# FMC_HPC_TO_LPC_BREAKOUT_REVA.net
KiCad netlist of a schematic drawn in Altium Designer
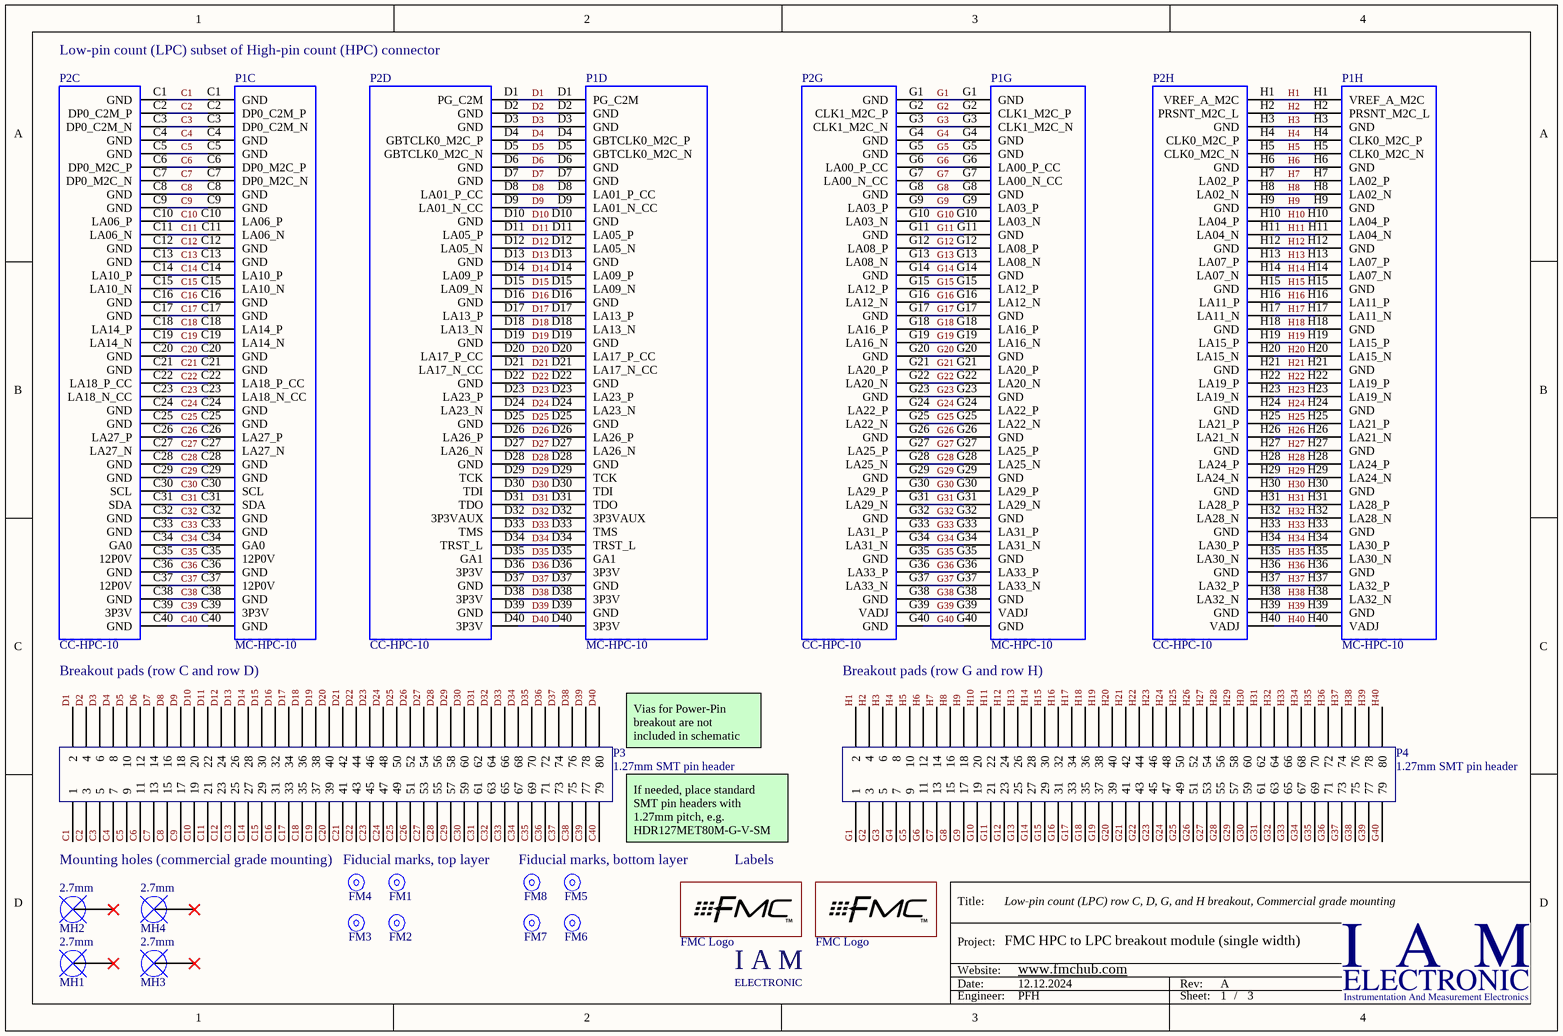
[diagram p0: FMC_HPC_TO_LPC_BREAKOUT_REVA.SchDoc]

(export (version "E")
  (design (tool "Eeschema 10.0.6"))
  (components
    (comp (ref "FM1")
      (value "1mm")
      (footprint "FIDUCIAL_MARK_ROUND_RING")
      (description "Fiducial mark, width 1mm, clearance 3mm")
      (libsource (lib "VITA_57_FMC") (part "Fiducial_Mark"))
    )
    (comp (ref "FM2")
      (value "1mm")
      (footprint "FIDUCIAL_MARK_ROUND_RING")
      (description "Fiducial mark, width 1mm, clearance 3mm")
      (libsource (lib "VITA_57_FMC") (part "Fiducial_Mark"))
    )
    (comp (ref "FM3")
      (value "1mm")
      (footprint "FIDUCIAL_MARK_ROUND_RING")
      (description "Fiducial mark, width 1mm, clearance 3mm")
      (libsource (lib "VITA_57_FMC") (part "Fiducial_Mark"))
    )
    (comp (ref "FM4")
      (value "1mm")
      (footprint "FIDUCIAL_MARK_ROUND_RING")
      (description "Fiducial mark, width 1mm, clearance 3mm")
      (libsource (lib "VITA_57_FMC") (part "Fiducial_Mark"))
    )
    (comp (ref "FM5")
      (value "1mm")
      (footprint "FIDUCIAL_MARK_ROUND_RING")
      (description "Fiducial mark, width 1mm, clearance 3mm")
      (libsource (lib "VITA_57_FMC") (part "Fiducial_Mark"))
    )
    (comp (ref "FM6")
      (value "1mm")
      (footprint "FIDUCIAL_MARK_ROUND_RING")
      (description "Fiducial mark, width 1mm, clearance 3mm")
      (libsource (lib "VITA_57_FMC") (part "Fiducial_Mark"))
    )
    (comp (ref "FM7")
      (value "1mm")
      (footprint "FIDUCIAL_MARK_ROUND_RING")
      (description "Fiducial mark, width 1mm, clearance 3mm")
      (libsource (lib "VITA_57_FMC") (part "Fiducial_Mark"))
    )
    (comp (ref "FM8")
      (value "1mm")
      (footprint "FIDUCIAL_MARK_ROUND_RING")
      (description "Fiducial mark, width 1mm, clearance 3mm")
      (libsource (lib "VITA_57_FMC") (part "Fiducial_Mark"))
    )
    (comp (ref "MH1")
      (value "2.7mm")
      (footprint "Mounting_Hole_Plated_2.7mm - d3.1mm")
      (description "Mounting hole, hole size 2.7mm")
      (libsource (lib "VITA_57_FMC") (part "Mounting_Hole_2.7mm"))
    )
    (comp (ref "MH2")
      (value "2.7mm")
      (footprint "Mounting_Hole_Plated_2.7mm - d3.1mm")
      (description "Mounting hole, hole size 2.7mm")
      (libsource (lib "VITA_57_FMC") (part "Mounting_Hole_2.7mm"))
    )
    (comp (ref "MH3")
      (value "2.7mm")
      (footprint "Mounting_Hole_Plated_2.7mm-COVERED")
      (description "Mounting hole, hole size 2.7mm")
      (libsource (lib "VITA_57_FMC") (part "Mounting_Hole_2.7mm"))
    )
    (comp (ref "MH4")
      (value "2.7mm")
      (footprint "Mounting_Hole_Plated_2.7mm-COVERED")
      (description "Mounting hole, hole size 2.7mm")
      (libsource (lib "VITA_57_FMC") (part "Mounting_Hole_2.7mm"))
    )
    (comp (ref "P1")
      (value "MC-HPC-10")
      (footprint "ASP-134488-01")
      (description "MC-HPC-10, FMC High-pin count connector, lead free, 400 I/Os, male, 10 mm mated stack height")
      (fields (field (name "MANUFACTURER") "Samtec") (field (name "PART") "ASP-134488-01"))
      (libsource (lib "VITA_57_FMC") (part "MC-HPC-10"))
    )
    (comp (ref "P2")
      (value "CC-HPC-10")
      (footprint "ASP-134486-01")
      (description "CC-HPC-10, FMC High-pin count connector, lead free, 400 I/Os, female, 10 mm mated stack height")
      (fields (field (name "MANUFACTURER") "Samtec") (field (name "PART") "ASP-134486-01"))
      (libsource (lib "VITA_57_FMC") (part "CC-HPC-10"))
    )
    (comp (ref "P3")
      (value "1.27mm SMT pin header")
      (footprint "FTS-140-01-L-DV-A_NO_PASTE")
      (description "1.27 MM 80 PIN VERTICAL MALE HEADER")
      (fields (field (name "PART") "FTS-140-01-L-DV-A") (field (name "MANUFACTURER") "Samtec"))
      (libsource (lib "FTS-140") (part "FTS-140-X-DV"))
    )
    (comp (ref "P4")
      (value "1.27mm SMT pin header")
      (footprint "FTS-140-01-L-DV-A_NO_PASTE")
      (description "1.27 MM 80 PIN VERTICAL MALE HEADER")
      (fields (field (name "PART") "FTS-140-01-L-DV-A") (field (name "MANUFACTURER") "Samtec"))
      (libsource (lib "FTS-140") (part "FTS-140-X-DV"))
    )
    (comp (ref "STR1")
      (value "IAM LOGO")
      (footprint "IAM LOGO - MEDIUM")
      (description "I A M E L E C T R O N I C - Logo")
      (fields (field (name "MANUFACTURER") "IAM ELECTRONIC") (field (name "PART") "Logo"))
      (libsource (lib "IAM_LOGOS") (part "IAM_LOGO"))
    )
    (comp (ref "STR2")
      (value "FMC Logo")
      (footprint "FMC_TM_LOGO_SMALL")
      (description "VITA FMC Logo")
      (libsource (lib "VITA_57_FMC") (part "FMC_Logo"))
    )
    (comp (ref "STR3")
      (value "FMC Logo")
      (footprint "FMC_TM_LOGO_SMALL")
      (description "VITA FMC Logo")
      (libsource (lib "VITA_57_FMC") (part "FMC_Logo"))
    )
  )
  (nets
    (net (code "1") (name "/C1") (class "Default")
      (node (ref "P1") (pin "C1") (pinfunction "GND_C1") (pintype "passive"))
      (node (ref "P2") (pin "C1") (pinfunction "GND_C1") (pintype "passive"))
      (node (ref "P3") (pin "1") (pinfunction "1_1") (pintype "passive"))
    )
    (net (code "2") (name "/C2") (class "Default")
      (node (ref "P1") (pin "C2") (pinfunction "DP0_C2M_P_C2") (pintype "passive"))
      (node (ref "P2") (pin "C2") (pinfunction "DP0_C2M_P_C2") (pintype "passive"))
      (node (ref "P3") (pin "3") (pinfunction "3_3") (pintype "passive"))
    )
    (net (code "3") (name "/C3") (class "Default")
      (node (ref "P1") (pin "C3") (pinfunction "DP0_C2M_N_C3") (pintype "passive"))
      (node (ref "P2") (pin "C3") (pinfunction "DP0_C2M_N_C3") (pintype "passive"))
      (node (ref "P3") (pin "5") (pinfunction "5_5") (pintype "passive"))
    )
    (net (code "4") (name "/C4") (class "Default")
      (node (ref "P1") (pin "C4") (pinfunction "GND_C4") (pintype "passive"))
      (node (ref "P2") (pin "C4") (pinfunction "GND_C4") (pintype "passive"))
      (node (ref "P3") (pin "7") (pinfunction "7_7") (pintype "passive"))
    )
    (net (code "5") (name "/C5") (class "Default")
      (node (ref "P1") (pin "C5") (pinfunction "GND_C5") (pintype "passive"))
      (node (ref "P2") (pin "C5") (pinfunction "GND_C5") (pintype "passive"))
      (node (ref "P3") (pin "9") (pinfunction "9_9") (pintype "passive"))
    )
    (net (code "6") (name "/C6") (class "Default")
      (node (ref "P1") (pin "C6") (pinfunction "DP0_M2C_P_C6") (pintype "passive"))
      (node (ref "P2") (pin "C6") (pinfunction "DP0_M2C_P_C6") (pintype "passive"))
      (node (ref "P3") (pin "11") (pinfunction "11_11") (pintype "passive"))
    )
    (net (code "7") (name "/C7") (class "Default")
      (node (ref "P1") (pin "C7") (pinfunction "DP0_M2C_N_C7") (pintype "passive"))
      (node (ref "P2") (pin "C7") (pinfunction "DP0_M2C_N_C7") (pintype "passive"))
      (node (ref "P3") (pin "13") (pinfunction "13_13") (pintype "passive"))
    )
    (net (code "8") (name "/C8") (class "Default")
      (node (ref "P1") (pin "C8") (pinfunction "GND_C8") (pintype "passive"))
      (node (ref "P2") (pin "C8") (pinfunction "GND_C8") (pintype "passive"))
      (node (ref "P3") (pin "15") (pinfunction "15_15") (pintype "passive"))
    )
    (net (code "9") (name "/C9") (class "Default")
      (node (ref "P1") (pin "C9") (pinfunction "GND_C9") (pintype "passive"))
      (node (ref "P2") (pin "C9") (pinfunction "GND_C9") (pintype "passive"))
      (node (ref "P3") (pin "17") (pinfunction "17_17") (pintype "passive"))
    )
    (net (code "10") (name "/C10") (class "Default")
      (node (ref "P1") (pin "C10") (pinfunction "LA06_P_C10") (pintype "passive"))
      (node (ref "P2") (pin "C10") (pinfunction "LA06_P_C10") (pintype "passive"))
      (node (ref "P3") (pin "19") (pinfunction "19_19") (pintype "passive"))
    )
    (net (code "11") (name "/C11") (class "Default")
      (node (ref "P1") (pin "C11") (pinfunction "LA06_N_C11") (pintype "passive"))
      (node (ref "P2") (pin "C11") (pinfunction "LA06_N_C11") (pintype "passive"))
      (node (ref "P3") (pin "21") (pinfunction "21_21") (pintype "passive"))
    )
    (net (code "12") (name "/C12") (class "Default")
      (node (ref "P1") (pin "C12") (pinfunction "GND_C12") (pintype "passive"))
      (node (ref "P2") (pin "C12") (pinfunction "GND_C12") (pintype "passive"))
      (node (ref "P3") (pin "23") (pinfunction "23_23") (pintype "passive"))
    )
    (net (code "13") (name "/C13") (class "Default")
      (node (ref "P1") (pin "C13") (pinfunction "GND_C13") (pintype "passive"))
      (node (ref "P2") (pin "C13") (pinfunction "GND_C13") (pintype "passive"))
      (node (ref "P3") (pin "25") (pinfunction "25_25") (pintype "passive"))
    )
    (net (code "14") (name "/C14") (class "Default")
      (node (ref "P1") (pin "C14") (pinfunction "LA10_P_C14") (pintype "passive"))
      (node (ref "P2") (pin "C14") (pinfunction "LA10_P_C14") (pintype "passive"))
      (node (ref "P3") (pin "27") (pinfunction "27_27") (pintype "passive"))
    )
    (net (code "15") (name "/C15") (class "Default")
      (node (ref "P1") (pin "C15") (pinfunction "LA10_N_C15") (pintype "passive"))
      (node (ref "P2") (pin "C15") (pinfunction "LA10_N_C15") (pintype "passive"))
      (node (ref "P3") (pin "29") (pinfunction "29_29") (pintype "passive"))
    )
    (net (code "16") (name "/C16") (class "Default")
      (node (ref "P1") (pin "C16") (pinfunction "GND_C16") (pintype "passive"))
      (node (ref "P2") (pin "C16") (pinfunction "GND_C16") (pintype "passive"))
      (node (ref "P3") (pin "31") (pinfunction "31_31") (pintype "passive"))
    )
    (net (code "17") (name "/C17") (class "Default")
      (node (ref "P1") (pin "C17") (pinfunction "GND_C17") (pintype "passive"))
      (node (ref "P2") (pin "C17") (pinfunction "GND_C17") (pintype "passive"))
      (node (ref "P3") (pin "33") (pinfunction "33_33") (pintype "passive"))
    )
    (net (code "18") (name "/C18") (class "Default")
      (node (ref "P1") (pin "C18") (pinfunction "LA14_P_C18") (pintype "passive"))
      (node (ref "P2") (pin "C18") (pinfunction "LA14_P_C18") (pintype "passive"))
      (node (ref "P3") (pin "35") (pinfunction "35_35") (pintype "passive"))
    )
    (net (code "19") (name "/C19") (class "Default")
      (node (ref "P1") (pin "C19") (pinfunction "LA14_N_C19") (pintype "passive"))
      (node (ref "P2") (pin "C19") (pinfunction "LA14_N_C19") (pintype "passive"))
      (node (ref "P3") (pin "37") (pinfunction "37_37") (pintype "passive"))
    )
    (net (code "20") (name "/C20") (class "Default")
      (node (ref "P1") (pin "C20") (pinfunction "GND_C20") (pintype "passive"))
      (node (ref "P2") (pin "C20") (pinfunction "GND_C20") (pintype "passive"))
      (node (ref "P3") (pin "39") (pinfunction "39_39") (pintype "passive"))
    )
    (net (code "21") (name "/C21") (class "Default")
      (node (ref "P1") (pin "C21") (pinfunction "GND_C21") (pintype "passive"))
      (node (ref "P2") (pin "C21") (pinfunction "GND_C21") (pintype "passive"))
      (node (ref "P3") (pin "41") (pinfunction "41_41") (pintype "passive"))
    )
    (net (code "22") (name "/C22") (class "Default")
      (node (ref "P1") (pin "C22") (pinfunction "LA18_P_CC_C22") (pintype "passive"))
      (node (ref "P2") (pin "C22") (pinfunction "LA18_P_CC_C22") (pintype "passive"))
      (node (ref "P3") (pin "43") (pinfunction "43_43") (pintype "passive"))
    )
    (net (code "23") (name "/C23") (class "Default")
      (node (ref "P1") (pin "C23") (pinfunction "LA18_N_CC_C23") (pintype "passive"))
      (node (ref "P2") (pin "C23") (pinfunction "LA18_N_CC_C23") (pintype "passive"))
      (node (ref "P3") (pin "45") (pinfunction "45_45") (pintype "passive"))
    )
    (net (code "24") (name "/C24") (class "Default")
      (node (ref "P1") (pin "C24") (pinfunction "GND_C24") (pintype "passive"))
      (node (ref "P2") (pin "C24") (pinfunction "GND_C24") (pintype "passive"))
      (node (ref "P3") (pin "47") (pinfunction "47_47") (pintype "passive"))
    )
    (net (code "25") (name "/C25") (class "Default")
      (node (ref "P1") (pin "C25") (pinfunction "GND_C25") (pintype "passive"))
      (node (ref "P2") (pin "C25") (pinfunction "GND_C25") (pintype "passive"))
      (node (ref "P3") (pin "49") (pinfunction "49_49") (pintype "passive"))
    )
    (net (code "26") (name "/C26") (class "Default")
      (node (ref "P1") (pin "C26") (pinfunction "LA27_P_C26") (pintype "passive"))
      (node (ref "P2") (pin "C26") (pinfunction "LA27_P_C26") (pintype "passive"))
      (node (ref "P3") (pin "51") (pinfunction "51_51") (pintype "passive"))
    )
    (net (code "27") (name "/C27") (class "Default")
      (node (ref "P1") (pin "C27") (pinfunction "LA27_N_C27") (pintype "passive"))
      (node (ref "P2") (pin "C27") (pinfunction "LA27_N_C27") (pintype "passive"))
      (node (ref "P3") (pin "53") (pinfunction "53_53") (pintype "passive"))
    )
    (net (code "28") (name "/C28") (class "Default")
      (node (ref "P1") (pin "C28") (pinfunction "GND_C28") (pintype "passive"))
      (node (ref "P2") (pin "C28") (pinfunction "GND_C28") (pintype "passive"))
      (node (ref "P3") (pin "55") (pinfunction "55_55") (pintype "passive"))
    )
    (net (code "29") (name "/C29") (class "Default")
      (node (ref "P1") (pin "C29") (pinfunction "GND_C29") (pintype "passive"))
      (node (ref "P2") (pin "C29") (pinfunction "GND_C29") (pintype "passive"))
      (node (ref "P3") (pin "57") (pinfunction "57_57") (pintype "passive"))
    )
    (net (code "30") (name "/C30") (class "Default")
      (node (ref "P1") (pin "C30") (pinfunction "SCL_C30") (pintype "passive"))
      (node (ref "P2") (pin "C30") (pinfunction "SCL_C30") (pintype "passive"))
      (node (ref "P3") (pin "59") (pinfunction "59_59") (pintype "passive"))
    )
    (net (code "31") (name "/C31") (class "Default")
      (node (ref "P1") (pin "C31") (pinfunction "SDA_C31") (pintype "passive"))
      (node (ref "P2") (pin "C31") (pinfunction "SDA_C31") (pintype "passive"))
      (node (ref "P3") (pin "61") (pinfunction "61_61") (pintype "passive"))
    )
    (net (code "32") (name "/C32") (class "Default")
      (node (ref "P1") (pin "C32") (pinfunction "GND_C32") (pintype "passive"))
      (node (ref "P2") (pin "C32") (pinfunction "GND_C32") (pintype "passive"))
      (node (ref "P3") (pin "63") (pinfunction "63_63") (pintype "passive"))
    )
    (net (code "33") (name "/C33") (class "Default")
      (node (ref "P1") (pin "C33") (pinfunction "GND_C33") (pintype "passive"))
      (node (ref "P2") (pin "C33") (pinfunction "GND_C33") (pintype "passive"))
      (node (ref "P3") (pin "65") (pinfunction "65_65") (pintype "passive"))
    )
    (net (code "34") (name "/C34") (class "Default")
      (node (ref "P1") (pin "C34") (pinfunction "GA0_C34") (pintype "passive"))
      (node (ref "P2") (pin "C34") (pinfunction "GA0_C34") (pintype "passive"))
      (node (ref "P3") (pin "67") (pinfunction "67_67") (pintype "passive"))
    )
    (net (code "35") (name "/C35") (class "Default")
      (node (ref "P1") (pin "C35") (pinfunction "12P0V_C35") (pintype "passive"))
      (node (ref "P2") (pin "C35") (pinfunction "12P0V_C35") (pintype "passive"))
      (node (ref "P3") (pin "69") (pinfunction "69_69") (pintype "passive"))
    )
    (net (code "36") (name "/C36") (class "Default")
      (node (ref "P1") (pin "C36") (pinfunction "GND_C36") (pintype "passive"))
      (node (ref "P2") (pin "C36") (pinfunction "GND_C36") (pintype "passive"))
      (node (ref "P3") (pin "71") (pinfunction "71_71") (pintype "passive"))
    )
    (net (code "37") (name "/C37") (class "Default")
      (node (ref "P1") (pin "C37") (pinfunction "12P0V_C37") (pintype "passive"))
      (node (ref "P2") (pin "C37") (pinfunction "12P0V_C37") (pintype "passive"))
      (node (ref "P3") (pin "73") (pinfunction "73_73") (pintype "passive"))
    )
    (net (code "38") (name "/C38") (class "Default")
      (node (ref "P1") (pin "C38") (pinfunction "GND_C38") (pintype "passive"))
      (node (ref "P2") (pin "C38") (pinfunction "GND_C38") (pintype "passive"))
      (node (ref "P3") (pin "75") (pinfunction "75_75") (pintype "passive"))
    )
    (net (code "39") (name "/C39") (class "Default")
      (node (ref "P1") (pin "C39") (pinfunction "3P3V_C39") (pintype "passive"))
      (node (ref "P2") (pin "C39") (pinfunction "3P3V_C39") (pintype "passive"))
      (node (ref "P3") (pin "77") (pinfunction "77_77") (pintype "passive"))
    )
    (net (code "40") (name "/C40") (class "Default")
      (node (ref "P1") (pin "C40") (pinfunction "GND_C40") (pintype "passive"))
      (node (ref "P2") (pin "C40") (pinfunction "GND_C40") (pintype "passive"))
      (node (ref "P3") (pin "79") (pinfunction "79_79") (pintype "passive"))
    )
    (net (code "41") (name "/D1") (class "Default")
      (node (ref "P1") (pin "D1") (pinfunction "PG_C2M_D1") (pintype "passive"))
      (node (ref "P2") (pin "D1") (pinfunction "PG_C2M_D1") (pintype "passive"))
      (node (ref "P3") (pin "2") (pinfunction "2_2") (pintype "passive"))
    )
    (net (code "42") (name "/D2") (class "Default")
      (node (ref "P1") (pin "D2") (pinfunction "GND_D2") (pintype "passive"))
      (node (ref "P2") (pin "D2") (pinfunction "GND_D2") (pintype "passive"))
      (node (ref "P3") (pin "4") (pinfunction "4_4") (pintype "passive"))
    )
    (net (code "43") (name "/D3") (class "Default")
      (node (ref "P1") (pin "D3") (pinfunction "GND_D3") (pintype "passive"))
      (node (ref "P2") (pin "D3") (pinfunction "GND_D3") (pintype "passive"))
      (node (ref "P3") (pin "6") (pinfunction "6_6") (pintype "passive"))
    )
    (net (code "44") (name "/D4") (class "Default")
      (node (ref "P1") (pin "D4") (pinfunction "GBTCLK0_M2C_P_D4") (pintype "passive"))
      (node (ref "P2") (pin "D4") (pinfunction "GBTCLK0_M2C_P_D4") (pintype "passive"))
      (node (ref "P3") (pin "8") (pinfunction "8_8") (pintype "passive"))
    )
    (net (code "45") (name "/D5") (class "Default")
      (node (ref "P1") (pin "D5") (pinfunction "GBTCLK0_M2C_N_D5") (pintype "passive"))
      (node (ref "P2") (pin "D5") (pinfunction "GBTCLK0_M2C_N_D5") (pintype "passive"))
      (node (ref "P3") (pin "10") (pinfunction "10_10") (pintype "passive"))
    )
    (net (code "46") (name "/D6") (class "Default")
      (node (ref "P1") (pin "D6") (pinfunction "GND_D6") (pintype "passive"))
      (node (ref "P2") (pin "D6") (pinfunction "GND_D6") (pintype "passive"))
      (node (ref "P3") (pin "12") (pinfunction "12_12") (pintype "passive"))
    )
    (net (code "47") (name "/D7") (class "Default")
      (node (ref "P1") (pin "D7") (pinfunction "GND_D7") (pintype "passive"))
      (node (ref "P2") (pin "D7") (pinfunction "GND_D7") (pintype "passive"))
      (node (ref "P3") (pin "14") (pinfunction "14_14") (pintype "passive"))
    )
    (net (code "48") (name "/D8") (class "Default")
      (node (ref "P1") (pin "D8") (pinfunction "LA01_P_CC_D8") (pintype "passive"))
      (node (ref "P2") (pin "D8") (pinfunction "LA01_P_CC_D8") (pintype "passive"))
      (node (ref "P3") (pin "16") (pinfunction "16_16") (pintype "passive"))
    )
    (net (code "49") (name "/D9") (class "Default")
      (node (ref "P1") (pin "D9") (pinfunction "LA01_N_CC_D9") (pintype "passive"))
      (node (ref "P2") (pin "D9") (pinfunction "LA01_N_CC_D9") (pintype "passive"))
      (node (ref "P3") (pin "18") (pinfunction "18_18") (pintype "passive"))
    )
    (net (code "50") (name "/D10") (class "Default")
      (node (ref "P1") (pin "D10") (pinfunction "GND_D10") (pintype "passive"))
      (node (ref "P2") (pin "D10") (pinfunction "GND_D10") (pintype "passive"))
      (node (ref "P3") (pin "20") (pinfunction "20_20") (pintype "passive"))
    )
    (net (code "51") (name "/D11") (class "Default")
      (node (ref "P1") (pin "D11") (pinfunction "LA05_P_D11") (pintype "passive"))
      (node (ref "P2") (pin "D11") (pinfunction "LA05_P_D11") (pintype "passive"))
      (node (ref "P3") (pin "22") (pinfunction "22_22") (pintype "passive"))
    )
    (net (code "52") (name "/D12") (class "Default")
      (node (ref "P1") (pin "D12") (pinfunction "LA05_N_D12") (pintype "passive"))
      (node (ref "P2") (pin "D12") (pinfunction "LA05_N_D12") (pintype "passive"))
      (node (ref "P3") (pin "24") (pinfunction "24_24") (pintype "passive"))
    )
    (net (code "53") (name "/D13") (class "Default")
      (node (ref "P1") (pin "D13") (pinfunction "GND_D13") (pintype "passive"))
      (node (ref "P2") (pin "D13") (pinfunction "GND_D13") (pintype "passive"))
      (node (ref "P3") (pin "26") (pinfunction "26_26") (pintype "passive"))
    )
    (net (code "54") (name "/D14") (class "Default")
      (node (ref "P1") (pin "D14") (pinfunction "LA09_P_D14") (pintype "passive"))
      (node (ref "P2") (pin "D14") (pinfunction "LA09_P_D14") (pintype "passive"))
      (node (ref "P3") (pin "28") (pinfunction "28_28") (pintype "passive"))
    )
    (net (code "55") (name "/D15") (class "Default")
      (node (ref "P1") (pin "D15") (pinfunction "LA09_N_D15") (pintype "passive"))
      (node (ref "P2") (pin "D15") (pinfunction "LA09_N_D15") (pintype "passive"))
      (node (ref "P3") (pin "30") (pinfunction "30_30") (pintype "passive"))
    )
    (net (code "56") (name "/D16") (class "Default")
      (node (ref "P1") (pin "D16") (pinfunction "GND_D16") (pintype "passive"))
      (node (ref "P2") (pin "D16") (pinfunction "GND_D16") (pintype "passive"))
      (node (ref "P3") (pin "32") (pinfunction "32_32") (pintype "passive"))
    )
    (net (code "57") (name "/D17") (class "Default")
      (node (ref "P1") (pin "D17") (pinfunction "LA13_P_D17") (pintype "passive"))
      (node (ref "P2") (pin "D17") (pinfunction "LA13_P_D17") (pintype "passive"))
      (node (ref "P3") (pin "34") (pinfunction "34_34") (pintype "passive"))
    )
    (net (code "58") (name "/D18") (class "Default")
      (node (ref "P1") (pin "D18") (pinfunction "LA13_N_D18") (pintype "passive"))
      (node (ref "P2") (pin "D18") (pinfunction "LA13_N_D18") (pintype "passive"))
      (node (ref "P3") (pin "36") (pinfunction "36_36") (pintype "passive"))
    )
    (net (code "59") (name "/D19") (class "Default")
      (node (ref "P1") (pin "D19") (pinfunction "GND_D19") (pintype "passive"))
      (node (ref "P2") (pin "D19") (pinfunction "GND_D19") (pintype "passive"))
      (node (ref "P3") (pin "38") (pinfunction "38_38") (pintype "passive"))
    )
    (net (code "60") (name "/D20") (class "Default")
      (node (ref "P1") (pin "D20") (pinfunction "LA17_P_CC_D20") (pintype "passive"))
      (node (ref "P2") (pin "D20") (pinfunction "LA17_P_CC_D20") (pintype "passive"))
      (node (ref "P3") (pin "40") (pinfunction "40_40") (pintype "passive"))
    )
    (net (code "61") (name "/D21") (class "Default")
      (node (ref "P1") (pin "D21") (pinfunction "LA17_N_CC_D21") (pintype "passive"))
      (node (ref "P2") (pin "D21") (pinfunction "LA17_N_CC_D21") (pintype "passive"))
      (node (ref "P3") (pin "42") (pinfunction "42_42") (pintype "passive"))
    )
    (net (code "62") (name "/D22") (class "Default")
      (node (ref "P1") (pin "D22") (pinfunction "GND_D22") (pintype "passive"))
      (node (ref "P2") (pin "D22") (pinfunction "GND_D22") (pintype "passive"))
      (node (ref "P3") (pin "44") (pinfunction "44_44") (pintype "passive"))
    )
    (net (code "63") (name "/D23") (class "Default")
      (node (ref "P1") (pin "D23") (pinfunction "LA23_P_D23") (pintype "passive"))
      (node (ref "P2") (pin "D23") (pinfunction "LA23_P_D23") (pintype "passive"))
      (node (ref "P3") (pin "46") (pinfunction "46_46") (pintype "passive"))
    )
    (net (code "64") (name "/D24") (class "Default")
      (node (ref "P1") (pin "D24") (pinfunction "LA23_N_D24") (pintype "passive"))
      (node (ref "P2") (pin "D24") (pinfunction "LA23_N_D24") (pintype "passive"))
      (node (ref "P3") (pin "48") (pinfunction "48_48") (pintype "passive"))
    )
    (net (code "65") (name "/D25") (class "Default")
      (node (ref "P1") (pin "D25") (pinfunction "GND_D25") (pintype "passive"))
      (node (ref "P2") (pin "D25") (pinfunction "GND_D25") (pintype "passive"))
      (node (ref "P3") (pin "50") (pinfunction "50_50") (pintype "passive"))
    )
    (net (code "66") (name "/D26") (class "Default")
      (node (ref "P1") (pin "D26") (pinfunction "LA26_P_D26") (pintype "passive"))
      (node (ref "P2") (pin "D26") (pinfunction "LA26_P_D26") (pintype "passive"))
      (node (ref "P3") (pin "52") (pinfunction "52_52") (pintype "passive"))
    )
    (net (code "67") (name "/D27") (class "Default")
      (node (ref "P1") (pin "D27") (pinfunction "LA26_N_D27") (pintype "passive"))
      (node (ref "P2") (pin "D27") (pinfunction "LA26_N_D27") (pintype "passive"))
      (node (ref "P3") (pin "54") (pinfunction "54_54") (pintype "passive"))
    )
    (net (code "68") (name "/D28") (class "Default")
      (node (ref "P1") (pin "D28") (pinfunction "GND_D28") (pintype "passive"))
      (node (ref "P2") (pin "D28") (pinfunction "GND_D28") (pintype "passive"))
      (node (ref "P3") (pin "56") (pinfunction "56_56") (pintype "passive"))
    )
    (net (code "69") (name "/D29") (class "Default")
      (node (ref "P1") (pin "D29") (pinfunction "TCK_D29") (pintype "passive"))
      (node (ref "P2") (pin "D29") (pinfunction "TCK_D29") (pintype "passive"))
      (node (ref "P3") (pin "58") (pinfunction "58_58") (pintype "passive"))
    )
    (net (code "70") (name "/D30") (class "Default")
      (node (ref "P1") (pin "D30") (pinfunction "TDI_D30") (pintype "passive"))
      (node (ref "P2") (pin "D30") (pinfunction "TDI_D30") (pintype "passive"))
      (node (ref "P3") (pin "60") (pinfunction "60_60") (pintype "passive"))
    )
    (net (code "71") (name "/D31") (class "Default")
      (node (ref "P1") (pin "D31") (pinfunction "TDO_D31") (pintype "passive"))
      (node (ref "P2") (pin "D31") (pinfunction "TDO_D31") (pintype "passive"))
      (node (ref "P3") (pin "62") (pinfunction "62_62") (pintype "passive"))
    )
    (net (code "72") (name "/D32") (class "Default")
      (node (ref "P1") (pin "D32") (pinfunction "3P3VAUX_D32") (pintype "passive"))
      (node (ref "P2") (pin "D32") (pinfunction "3P3VAUX_D32") (pintype "passive"))
      (node (ref "P3") (pin "64") (pinfunction "64_64") (pintype "passive"))
    )
    (net (code "73") (name "/D33") (class "Default")
      (node (ref "P1") (pin "D33") (pinfunction "TMS_D33") (pintype "passive"))
      (node (ref "P2") (pin "D33") (pinfunction "TMS_D33") (pintype "passive"))
      (node (ref "P3") (pin "66") (pinfunction "66_66") (pintype "passive"))
    )
    (net (code "74") (name "/D34") (class "Default")
      (node (ref "P1") (pin "D34") (pinfunction "TRST_L_D34") (pintype "passive"))
      (node (ref "P2") (pin "D34") (pinfunction "TRST_L_D34") (pintype "passive"))
      (node (ref "P3") (pin "68") (pinfunction "68_68") (pintype "passive"))
    )
    (net (code "75") (name "/D35") (class "Default")
      (node (ref "P1") (pin "D35") (pinfunction "GA1_D35") (pintype "passive"))
      (node (ref "P2") (pin "D35") (pinfunction "GA1_D35") (pintype "passive"))
      (node (ref "P3") (pin "70") (pinfunction "70_70") (pintype "passive"))
    )
    (net (code "76") (name "/D36") (class "Default")
      (node (ref "P1") (pin "D36") (pinfunction "3P3V_D36") (pintype "passive"))
      (node (ref "P2") (pin "D36") (pinfunction "3P3V_D36") (pintype "passive"))
      (node (ref "P3") (pin "72") (pinfunction "72_72") (pintype "passive"))
    )
    (net (code "77") (name "/D37") (class "Default")
      (node (ref "P1") (pin "D37") (pinfunction "GND_D37") (pintype "passive"))
      (node (ref "P2") (pin "D37") (pinfunction "GND_D37") (pintype "passive"))
      (node (ref "P3") (pin "74") (pinfunction "74_74") (pintype "passive"))
    )
    (net (code "78") (name "/D38") (class "Default")
      (node (ref "P1") (pin "D38") (pinfunction "3P3V_D38") (pintype "passive"))
      (node (ref "P2") (pin "D38") (pinfunction "3P3V_D38") (pintype "passive"))
      (node (ref "P3") (pin "76") (pinfunction "76_76") (pintype "passive"))
    )
    (net (code "79") (name "/D39") (class "Default")
      (node (ref "P1") (pin "D39") (pinfunction "GND_D39") (pintype "passive"))
      (node (ref "P2") (pin "D39") (pinfunction "GND_D39") (pintype "passive"))
      (node (ref "P3") (pin "78") (pinfunction "78_78") (pintype "passive"))
    )
    (net (code "80") (name "/D40") (class "Default")
      (node (ref "P1") (pin "D40") (pinfunction "3P3V_D40") (pintype "passive"))
      (node (ref "P2") (pin "D40") (pinfunction "3P3V_D40") (pintype "passive"))
      (node (ref "P3") (pin "80") (pinfunction "80_80") (pintype "passive"))
    )
    (net (code "81") (name "/G1") (class "Default")
      (node (ref "P1") (pin "G1") (pinfunction "GND_G1") (pintype "passive"))
      (node (ref "P2") (pin "G1") (pinfunction "GND_G1") (pintype "passive"))
      (node (ref "P4") (pin "1") (pinfunction "1_1") (pintype "passive"))
    )
    (net (code "82") (name "/G2") (class "Default")
      (node (ref "P1") (pin "G2") (pinfunction "CLK1_M2C_P_G2") (pintype "passive"))
      (node (ref "P2") (pin "G2") (pinfunction "CLK1_M2C_P_G2") (pintype "passive"))
      (node (ref "P4") (pin "3") (pinfunction "3_3") (pintype "passive"))
    )
    (net (code "83") (name "/G3") (class "Default")
      (node (ref "P1") (pin "G3") (pinfunction "CLK1_M2C_N_G3") (pintype "passive"))
      (node (ref "P2") (pin "G3") (pinfunction "CLK1_M2C_N_G3") (pintype "passive"))
      (node (ref "P4") (pin "5") (pinfunction "5_5") (pintype "passive"))
    )
    (net (code "84") (name "/G4") (class "Default")
      (node (ref "P1") (pin "G4") (pinfunction "GND_G4") (pintype "passive"))
      (node (ref "P2") (pin "G4") (pinfunction "GND_G4") (pintype "passive"))
      (node (ref "P4") (pin "7") (pinfunction "7_7") (pintype "passive"))
    )
    (net (code "85") (name "/G5") (class "Default")
      (node (ref "P1") (pin "G5") (pinfunction "GND_G5") (pintype "passive"))
      (node (ref "P2") (pin "G5") (pinfunction "GND_G5") (pintype "passive"))
      (node (ref "P4") (pin "9") (pinfunction "9_9") (pintype "passive"))
    )
    (net (code "86") (name "/G6") (class "Default")
      (node (ref "P1") (pin "G6") (pinfunction "LA00_P_CC_G6") (pintype "passive"))
      (node (ref "P2") (pin "G6") (pinfunction "LA00_P_CC_G6") (pintype "passive"))
      (node (ref "P4") (pin "11") (pinfunction "11_11") (pintype "passive"))
    )
    (net (code "87") (name "/G7") (class "Default")
      (node (ref "P1") (pin "G7") (pinfunction "LA00_N_CC_G7") (pintype "passive"))
      (node (ref "P2") (pin "G7") (pinfunction "LA00_N_CC_G7") (pintype "passive"))
      (node (ref "P4") (pin "13") (pinfunction "13_13") (pintype "passive"))
    )
    (net (code "88") (name "/G8") (class "Default")
      (node (ref "P1") (pin "G8") (pinfunction "GND_G8") (pintype "passive"))
      (node (ref "P2") (pin "G8") (pinfunction "GND_G8") (pintype "passive"))
      (node (ref "P4") (pin "15") (pinfunction "15_15") (pintype "passive"))
    )
    (net (code "89") (name "/G9") (class "Default")
      (node (ref "P1") (pin "G9") (pinfunction "LA03_P_G9") (pintype "passive"))
      (node (ref "P2") (pin "G9") (pinfunction "LA03_P_G9") (pintype "passive"))
      (node (ref "P4") (pin "17") (pinfunction "17_17") (pintype "passive"))
    )
    (net (code "90") (name "/G10") (class "Default")
      (node (ref "P1") (pin "G10") (pinfunction "LA03_N_G10") (pintype "passive"))
      (node (ref "P2") (pin "G10") (pinfunction "LA03_N_G10") (pintype "passive"))
      (node (ref "P4") (pin "19") (pinfunction "19_19") (pintype "passive"))
    )
    (net (code "91") (name "/G11") (class "Default")
      (node (ref "P1") (pin "G11") (pinfunction "GND_G11") (pintype "passive"))
      (node (ref "P2") (pin "G11") (pinfunction "GND_G11") (pintype "passive"))
      (node (ref "P4") (pin "21") (pinfunction "21_21") (pintype "passive"))
    )
    (net (code "92") (name "/G12") (class "Default")
      (node (ref "P1") (pin "G12") (pinfunction "LA08_P_G12") (pintype "passive"))
      (node (ref "P2") (pin "G12") (pinfunction "LA08_P_G12") (pintype "passive"))
      (node (ref "P4") (pin "23") (pinfunction "23_23") (pintype "passive"))
    )
    (net (code "93") (name "/G13") (class "Default")
      (node (ref "P1") (pin "G13") (pinfunction "LA08_N_G13") (pintype "passive"))
      (node (ref "P2") (pin "G13") (pinfunction "LA08_N_G13") (pintype "passive"))
      (node (ref "P4") (pin "25") (pinfunction "25_25") (pintype "passive"))
    )
    (net (code "94") (name "/G14") (class "Default")
      (node (ref "P1") (pin "G14") (pinfunction "GND_G14") (pintype "passive"))
      (node (ref "P2") (pin "G14") (pinfunction "GND_G14") (pintype "passive"))
      (node (ref "P4") (pin "27") (pinfunction "27_27") (pintype "passive"))
    )
    (net (code "95") (name "/G15") (class "Default")
      (node (ref "P1") (pin "G15") (pinfunction "LA12_P_G15") (pintype "passive"))
      (node (ref "P2") (pin "G15") (pinfunction "LA12_P_G15") (pintype "passive"))
      (node (ref "P4") (pin "29") (pinfunction "29_29") (pintype "passive"))
    )
    (net (code "96") (name "/G16") (class "Default")
      (node (ref "P1") (pin "G16") (pinfunction "LA12_N_G16") (pintype "passive"))
      (node (ref "P2") (pin "G16") (pinfunction "LA12_N_G16") (pintype "passive"))
      (node (ref "P4") (pin "31") (pinfunction "31_31") (pintype "passive"))
    )
    (net (code "97") (name "/G17") (class "Default")
      (node (ref "P1") (pin "G17") (pinfunction "GND_G17") (pintype "passive"))
      (node (ref "P2") (pin "G17") (pinfunction "GND_G17") (pintype "passive"))
      (node (ref "P4") (pin "33") (pinfunction "33_33") (pintype "passive"))
    )
    (net (code "98") (name "/G18") (class "Default")
      (node (ref "P1") (pin "G18") (pinfunction "LA16_P_G18") (pintype "passive"))
      (node (ref "P2") (pin "G18") (pinfunction "LA16_P_G18") (pintype "passive"))
      (node (ref "P4") (pin "35") (pinfunction "35_35") (pintype "passive"))
    )
    (net (code "99") (name "/G19") (class "Default")
      (node (ref "P1") (pin "G19") (pinfunction "LA16_N_G19") (pintype "passive"))
      (node (ref "P2") (pin "G19") (pinfunction "LA16_N_G19") (pintype "passive"))
      (node (ref "P4") (pin "37") (pinfunction "37_37") (pintype "passive"))
    )
    (net (code "100") (name "/G20") (class "Default")
      (node (ref "P1") (pin "G20") (pinfunction "GND_G20") (pintype "passive"))
      (node (ref "P2") (pin "G20") (pinfunction "GND_G20") (pintype "passive"))
      (node (ref "P4") (pin "39") (pinfunction "39_39") (pintype "passive"))
    )
    (net (code "101") (name "/G21") (class "Default")
      (node (ref "P1") (pin "G21") (pinfunction "LA20_P_G21") (pintype "passive"))
      (node (ref "P2") (pin "G21") (pinfunction "LA20_P_G21") (pintype "passive"))
      (node (ref "P4") (pin "41") (pinfunction "41_41") (pintype "passive"))
    )
    (net (code "102") (name "/G22") (class "Default")
      (node (ref "P1") (pin "G22") (pinfunction "LA20_N_G22") (pintype "passive"))
      (node (ref "P2") (pin "G22") (pinfunction "LA20_N_G22") (pintype "passive"))
      (node (ref "P4") (pin "43") (pinfunction "43_43") (pintype "passive"))
    )
    (net (code "103") (name "/G23") (class "Default")
      (node (ref "P1") (pin "G23") (pinfunction "GND_G23") (pintype "passive"))
      (node (ref "P2") (pin "G23") (pinfunction "GND_G23") (pintype "passive"))
      (node (ref "P4") (pin "45") (pinfunction "45_45") (pintype "passive"))
    )
    (net (code "104") (name "/G24") (class "Default")
      (node (ref "P1") (pin "G24") (pinfunction "LA22_P_G24") (pintype "passive"))
      (node (ref "P2") (pin "G24") (pinfunction "LA22_P_G24") (pintype "passive"))
      (node (ref "P4") (pin "47") (pinfunction "47_47") (pintype "passive"))
    )
    (net (code "105") (name "/G25") (class "Default")
      (node (ref "P1") (pin "G25") (pinfunction "LA22_N_G25") (pintype "passive"))
      (node (ref "P2") (pin "G25") (pinfunction "LA22_N_G25") (pintype "passive"))
      (node (ref "P4") (pin "49") (pinfunction "49_49") (pintype "passive"))
    )
    (net (code "106") (name "/G26") (class "Default")
      (node (ref "P1") (pin "G26") (pinfunction "GND_G26") (pintype "passive"))
      (node (ref "P2") (pin "G26") (pinfunction "GND_G26") (pintype "passive"))
      (node (ref "P4") (pin "51") (pinfunction "51_51") (pintype "passive"))
    )
    (net (code "107") (name "/G27") (class "Default")
      (node (ref "P1") (pin "G27") (pinfunction "LA25_P_G27") (pintype "passive"))
      (node (ref "P2") (pin "G27") (pinfunction "LA25_P_G27") (pintype "passive"))
      (node (ref "P4") (pin "53") (pinfunction "53_53") (pintype "passive"))
    )
    (net (code "108") (name "/G28") (class "Default")
      (node (ref "P1") (pin "G28") (pinfunction "LA25_N_G28") (pintype "passive"))
      (node (ref "P2") (pin "G28") (pinfunction "LA25_N_G28") (pintype "passive"))
      (node (ref "P4") (pin "55") (pinfunction "55_55") (pintype "passive"))
    )
    (net (code "109") (name "/G29") (class "Default")
      (node (ref "P1") (pin "G29") (pinfunction "GND_G29") (pintype "passive"))
      (node (ref "P2") (pin "G29") (pinfunction "GND_G29") (pintype "passive"))
      (node (ref "P4") (pin "57") (pinfunction "57_57") (pintype "passive"))
    )
    (net (code "110") (name "/G30") (class "Default")
      (node (ref "P1") (pin "G30") (pinfunction "LA29_P_G30") (pintype "passive"))
      (node (ref "P2") (pin "G30") (pinfunction "LA29_P_G30") (pintype "passive"))
      (node (ref "P4") (pin "59") (pinfunction "59_59") (pintype "passive"))
    )
    (net (code "111") (name "/G31") (class "Default")
      (node (ref "P1") (pin "G31") (pinfunction "LA29_N_G31") (pintype "passive"))
      (node (ref "P2") (pin "G31") (pinfunction "LA29_N_G31") (pintype "passive"))
      (node (ref "P4") (pin "61") (pinfunction "61_61") (pintype "passive"))
    )
    (net (code "112") (name "/G32") (class "Default")
      (node (ref "P1") (pin "G32") (pinfunction "GND_G32") (pintype "passive"))
      (node (ref "P2") (pin "G32") (pinfunction "GND_G32") (pintype "passive"))
      (node (ref "P4") (pin "63") (pinfunction "63_63") (pintype "passive"))
    )
    (net (code "113") (name "/G33") (class "Default")
      (node (ref "P1") (pin "G33") (pinfunction "LA31_P_G33") (pintype "passive"))
      (node (ref "P2") (pin "G33") (pinfunction "LA31_P_G33") (pintype "passive"))
      (node (ref "P4") (pin "65") (pinfunction "65_65") (pintype "passive"))
    )
    (net (code "114") (name "/G34") (class "Default")
      (node (ref "P1") (pin "G34") (pinfunction "LA31_N_G34") (pintype "passive"))
      (node (ref "P2") (pin "G34") (pinfunction "LA31_N_G34") (pintype "passive"))
      (node (ref "P4") (pin "67") (pinfunction "67_67") (pintype "passive"))
    )
    (net (code "115") (name "/G35") (class "Default")
      (node (ref "P1") (pin "G35") (pinfunction "GND_G35") (pintype "passive"))
      (node (ref "P2") (pin "G35") (pinfunction "GND_G35") (pintype "passive"))
      (node (ref "P4") (pin "69") (pinfunction "69_69") (pintype "passive"))
    )
    (net (code "116") (name "/G36") (class "Default")
      (node (ref "P1") (pin "G36") (pinfunction "LA33_P_G36") (pintype "passive"))
      (node (ref "P2") (pin "G36") (pinfunction "LA33_P_G36") (pintype "passive"))
      (node (ref "P4") (pin "71") (pinfunction "71_71") (pintype "passive"))
    )
    (net (code "117") (name "/G37") (class "Default")
      (node (ref "P1") (pin "G37") (pinfunction "LA33_N_G37") (pintype "passive"))
      (node (ref "P2") (pin "G37") (pinfunction "LA33_N_G37") (pintype "passive"))
      (node (ref "P4") (pin "73") (pinfunction "73_73") (pintype "passive"))
    )
    (net (code "118") (name "/G38") (class "Default")
      (node (ref "P1") (pin "G38") (pinfunction "GND_G38") (pintype "passive"))
      (node (ref "P2") (pin "G38") (pinfunction "GND_G38") (pintype "passive"))
      (node (ref "P4") (pin "75") (pinfunction "75_75") (pintype "passive"))
    )
    (net (code "119") (name "/G39") (class "Default")
      (node (ref "P1") (pin "G39") (pinfunction "VADJ_G39") (pintype "passive"))
      (node (ref "P2") (pin "G39") (pinfunction "VADJ_G39") (pintype "passive"))
      (node (ref "P4") (pin "77") (pinfunction "77_77") (pintype "passive"))
    )
    (net (code "120") (name "/G40") (class "Default")
      (node (ref "P1") (pin "G40") (pinfunction "GND_G40") (pintype "passive"))
      (node (ref "P2") (pin "G40") (pinfunction "GND_G40") (pintype "passive"))
      (node (ref "P4") (pin "79") (pinfunction "79_79") (pintype "passive"))
    )
    (net (code "121") (name "/H1") (class "Default")
      (node (ref "P1") (pin "H1") (pinfunction "VREF_A_M2C_H1") (pintype "passive"))
      (node (ref "P2") (pin "H1") (pinfunction "VREF_A_M2C_H1") (pintype "passive"))
      (node (ref "P4") (pin "2") (pinfunction "2_2") (pintype "passive"))
    )
    (net (code "122") (name "/H2") (class "Default")
      (node (ref "P1") (pin "H2") (pinfunction "PRSNT_M2C_L_H2") (pintype "passive"))
      (node (ref "P2") (pin "H2") (pinfunction "PRSNT_M2C_L_H2") (pintype "passive"))
      (node (ref "P4") (pin "4") (pinfunction "4_4") (pintype "passive"))
    )
    (net (code "123") (name "/H3") (class "Default")
      (node (ref "P1") (pin "H3") (pinfunction "GND_H3") (pintype "passive"))
      (node (ref "P2") (pin "H3") (pinfunction "GND_H3") (pintype "passive"))
      (node (ref "P4") (pin "6") (pinfunction "6_6") (pintype "passive"))
    )
    (net (code "124") (name "/H4") (class "Default")
      (node (ref "P1") (pin "H4") (pinfunction "CLK0_M2C_P_H4") (pintype "passive"))
      (node (ref "P2") (pin "H4") (pinfunction "CLK0_M2C_P_H4") (pintype "passive"))
      (node (ref "P4") (pin "8") (pinfunction "8_8") (pintype "passive"))
    )
    (net (code "125") (name "/H5") (class "Default")
      (node (ref "P1") (pin "H5") (pinfunction "CLK0_M2C_N_H5") (pintype "passive"))
      (node (ref "P2") (pin "H5") (pinfunction "CLK0_M2C_N_H5") (pintype "passive"))
      (node (ref "P4") (pin "10") (pinfunction "10_10") (pintype "passive"))
    )
    (net (code "126") (name "/H6") (class "Default")
      (node (ref "P1") (pin "H6") (pinfunction "GND_H6") (pintype "passive"))
      (node (ref "P2") (pin "H6") (pinfunction "GND_H6") (pintype "passive"))
      (node (ref "P4") (pin "12") (pinfunction "12_12") (pintype "passive"))
    )
    (net (code "127") (name "/H7") (class "Default")
      (node (ref "P1") (pin "H7") (pinfunction "LA02_P_H7") (pintype "passive"))
      (node (ref "P2") (pin "H7") (pinfunction "LA02_P_H7") (pintype "passive"))
      (node (ref "P4") (pin "14") (pinfunction "14_14") (pintype "passive"))
    )
    (net (code "128") (name "/H8") (class "Default")
      (node (ref "P1") (pin "H8") (pinfunction "LA02_N_H8") (pintype "passive"))
      (node (ref "P2") (pin "H8") (pinfunction "LA02_N_H8") (pintype "passive"))
      (node (ref "P4") (pin "16") (pinfunction "16_16") (pintype "passive"))
    )
    (net (code "129") (name "/H9") (class "Default")
      (node (ref "P1") (pin "H9") (pinfunction "GND_H9") (pintype "passive"))
      (node (ref "P2") (pin "H9") (pinfunction "GND_H9") (pintype "passive"))
      (node (ref "P4") (pin "18") (pinfunction "18_18") (pintype "passive"))
    )
    (net (code "130") (name "/H10") (class "Default")
      (node (ref "P1") (pin "H10") (pinfunction "LA04_P_H10") (pintype "passive"))
      (node (ref "P2") (pin "H10") (pinfunction "LA04_P_H10") (pintype "passive"))
      (node (ref "P4") (pin "20") (pinfunction "20_20") (pintype "passive"))
    )
    (net (code "131") (name "/H11") (class "Default")
      (node (ref "P1") (pin "H11") (pinfunction "LA04_N_H11") (pintype "passive"))
      (node (ref "P2") (pin "H11") (pinfunction "LA04_N_H11") (pintype "passive"))
      (node (ref "P4") (pin "22") (pinfunction "22_22") (pintype "passive"))
    )
    (net (code "132") (name "/H12") (class "Default")
      (node (ref "P1") (pin "H12") (pinfunction "GND_H12") (pintype "passive"))
      (node (ref "P2") (pin "H12") (pinfunction "GND_H12") (pintype "passive"))
      (node (ref "P4") (pin "24") (pinfunction "24_24") (pintype "passive"))
    )
    (net (code "133") (name "/H13") (class "Default")
      (node (ref "P1") (pin "H13") (pinfunction "LA07_P_H13") (pintype "passive"))
      (node (ref "P2") (pin "H13") (pinfunction "LA07_P_H13") (pintype "passive"))
      (node (ref "P4") (pin "26") (pinfunction "26_26") (pintype "passive"))
    )
    (net (code "134") (name "/H14") (class "Default")
      (node (ref "P1") (pin "H14") (pinfunction "LA07_N_H14") (pintype "passive"))
      (node (ref "P2") (pin "H14") (pinfunction "LA07_N_H14") (pintype "passive"))
      (node (ref "P4") (pin "28") (pinfunction "28_28") (pintype "passive"))
    )
    (net (code "135") (name "/H15") (class "Default")
      (node (ref "P1") (pin "H15") (pinfunction "GND_H15") (pintype "passive"))
      (node (ref "P2") (pin "H15") (pinfunction "GND_H15") (pintype "passive"))
      (node (ref "P4") (pin "30") (pinfunction "30_30") (pintype "passive"))
    )
    (net (code "136") (name "/H16") (class "Default")
      (node (ref "P1") (pin "H16") (pinfunction "LA11_P_H16") (pintype "passive"))
      (node (ref "P2") (pin "H16") (pinfunction "LA11_P_H16") (pintype "passive"))
      (node (ref "P4") (pin "32") (pinfunction "32_32") (pintype "passive"))
    )
    (net (code "137") (name "/H17") (class "Default")
      (node (ref "P1") (pin "H17") (pinfunction "LA11_N_H17") (pintype "passive"))
      (node (ref "P2") (pin "H17") (pinfunction "LA11_N_H17") (pintype "passive"))
      (node (ref "P4") (pin "34") (pinfunction "34_34") (pintype "passive"))
    )
    (net (code "138") (name "/H18") (class "Default")
      (node (ref "P1") (pin "H18") (pinfunction "GND_H18") (pintype "passive"))
      (node (ref "P2") (pin "H18") (pinfunction "GND_H18") (pintype "passive"))
      (node (ref "P4") (pin "36") (pinfunction "36_36") (pintype "passive"))
    )
    (net (code "139") (name "/H19") (class "Default")
      (node (ref "P1") (pin "H19") (pinfunction "LA15_P_H19") (pintype "passive"))
      (node (ref "P2") (pin "H19") (pinfunction "LA15_P_H19") (pintype "passive"))
      (node (ref "P4") (pin "38") (pinfunction "38_38") (pintype "passive"))
    )
    (net (code "140") (name "/H20") (class "Default")
      (node (ref "P1") (pin "H20") (pinfunction "LA15_N_H20") (pintype "passive"))
      (node (ref "P2") (pin "H20") (pinfunction "LA15_N_H20") (pintype "passive"))
      (node (ref "P4") (pin "40") (pinfunction "40_40") (pintype "passive"))
    )
    (net (code "141") (name "/H21") (class "Default")
      (node (ref "P1") (pin "H21") (pinfunction "GND_H21") (pintype "passive"))
      (node (ref "P2") (pin "H21") (pinfunction "GND_H21") (pintype "passive"))
      (node (ref "P4") (pin "42") (pinfunction "42_42") (pintype "passive"))
    )
    (net (code "142") (name "/H22") (class "Default")
      (node (ref "P1") (pin "H22") (pinfunction "LA19_P_H22") (pintype "passive"))
      (node (ref "P2") (pin "H22") (pinfunction "LA19_P_H22") (pintype "passive"))
      (node (ref "P4") (pin "44") (pinfunction "44_44") (pintype "passive"))
    )
    (net (code "143") (name "/H23") (class "Default")
      (node (ref "P1") (pin "H23") (pinfunction "LA19_N_H23") (pintype "passive"))
      (node (ref "P2") (pin "H23") (pinfunction "LA19_N_H23") (pintype "passive"))
      (node (ref "P4") (pin "46") (pinfunction "46_46") (pintype "passive"))
    )
    (net (code "144") (name "/H24") (class "Default")
      (node (ref "P1") (pin "H24") (pinfunction "GND_H24") (pintype "passive"))
      (node (ref "P2") (pin "H24") (pinfunction "GND_H24") (pintype "passive"))
      (node (ref "P4") (pin "48") (pinfunction "48_48") (pintype "passive"))
    )
    (net (code "145") (name "/H25") (class "Default")
      (node (ref "P1") (pin "H25") (pinfunction "LA21_P_H25") (pintype "passive"))
      (node (ref "P2") (pin "H25") (pinfunction "LA21_P_H25") (pintype "passive"))
      (node (ref "P4") (pin "50") (pinfunction "50_50") (pintype "passive"))
    )
    (net (code "146") (name "/H26") (class "Default")
      (node (ref "P1") (pin "H26") (pinfunction "LA21_N_H26") (pintype "passive"))
      (node (ref "P2") (pin "H26") (pinfunction "LA21_N_H26") (pintype "passive"))
      (node (ref "P4") (pin "52") (pinfunction "52_52") (pintype "passive"))
    )
    (net (code "147") (name "/H27") (class "Default")
      (node (ref "P1") (pin "H27") (pinfunction "GND_H27") (pintype "passive"))
      (node (ref "P2") (pin "H27") (pinfunction "GND_H27") (pintype "passive"))
      (node (ref "P4") (pin "54") (pinfunction "54_54") (pintype "passive"))
    )
    (net (code "148") (name "/H28") (class "Default")
      (node (ref "P1") (pin "H28") (pinfunction "LA24_P_H28") (pintype "passive"))
      (node (ref "P2") (pin "H28") (pinfunction "LA24_P_H28") (pintype "passive"))
      (node (ref "P4") (pin "56") (pinfunction "56_56") (pintype "passive"))
    )
    (net (code "149") (name "/H29") (class "Default")
      (node (ref "P1") (pin "H29") (pinfunction "LA24_N_H29") (pintype "passive"))
      (node (ref "P2") (pin "H29") (pinfunction "LA24_N_H29") (pintype "passive"))
      (node (ref "P4") (pin "58") (pinfunction "58_58") (pintype "passive"))
    )
    (net (code "150") (name "/H30") (class "Default")
      (node (ref "P1") (pin "H30") (pinfunction "GND_H30") (pintype "passive"))
      (node (ref "P2") (pin "H30") (pinfunction "GND_H30") (pintype "passive"))
      (node (ref "P4") (pin "60") (pinfunction "60_60") (pintype "passive"))
    )
    (net (code "151") (name "/H31") (class "Default")
      (node (ref "P1") (pin "H31") (pinfunction "LA28_P_H31") (pintype "passive"))
      (node (ref "P2") (pin "H31") (pinfunction "LA28_P_H31") (pintype "passive"))
      (node (ref "P4") (pin "62") (pinfunction "62_62") (pintype "passive"))
    )
    (net (code "152") (name "/H32") (class "Default")
      (node (ref "P1") (pin "H32") (pinfunction "LA28_N_H32") (pintype "passive"))
      (node (ref "P2") (pin "H32") (pinfunction "LA28_N_H32") (pintype "passive"))
      (node (ref "P4") (pin "64") (pinfunction "64_64") (pintype "passive"))
    )
    (net (code "153") (name "/H33") (class "Default")
      (node (ref "P1") (pin "H33") (pinfunction "GND_H33") (pintype "passive"))
      (node (ref "P2") (pin "H33") (pinfunction "GND_H33") (pintype "passive"))
      (node (ref "P4") (pin "66") (pinfunction "66_66") (pintype "passive"))
    )
    (net (code "154") (name "/H34") (class "Default")
      (node (ref "P1") (pin "H34") (pinfunction "LA30_P_H34") (pintype "passive"))
      (node (ref "P2") (pin "H34") (pinfunction "LA30_P_H34") (pintype "passive"))
      (node (ref "P4") (pin "68") (pinfunction "68_68") (pintype "passive"))
    )
    (net (code "155") (name "/H35") (class "Default")
      (node (ref "P1") (pin "H35") (pinfunction "LA30_N_H35") (pintype "passive"))
      (node (ref "P2") (pin "H35") (pinfunction "LA30_N_H35") (pintype "passive"))
      (node (ref "P4") (pin "70") (pinfunction "70_70") (pintype "passive"))
    )
    (net (code "156") (name "/H36") (class "Default")
      (node (ref "P1") (pin "H36") (pinfunction "GND_H36") (pintype "passive"))
      (node (ref "P2") (pin "H36") (pinfunction "GND_H36") (pintype "passive"))
      (node (ref "P4") (pin "72") (pinfunction "72_72") (pintype "passive"))
    )
    (net (code "157") (name "/H37") (class "Default")
      (node (ref "P1") (pin "H37") (pinfunction "LA32_P_H37") (pintype "passive"))
      (node (ref "P2") (pin "H37") (pinfunction "LA32_P_H37") (pintype "passive"))
      (node (ref "P4") (pin "74") (pinfunction "74_74") (pintype "passive"))
    )
    (net (code "158") (name "/H38") (class "Default")
      (node (ref "P1") (pin "H38") (pinfunction "LA32_N_H38") (pintype "passive"))
      (node (ref "P2") (pin "H38") (pinfunction "LA32_N_H38") (pintype "passive"))
      (node (ref "P4") (pin "76") (pinfunction "76_76") (pintype "passive"))
    )
    (net (code "159") (name "/H39") (class "Default")
      (node (ref "P1") (pin "H39") (pinfunction "GND_H39") (pintype "passive"))
      (node (ref "P2") (pin "H39") (pinfunction "GND_H39") (pintype "passive"))
      (node (ref "P4") (pin "78") (pinfunction "78_78") (pintype "passive"))
    )
    (net (code "160") (name "/H40") (class "Default")
      (node (ref "P1") (pin "H40") (pinfunction "VADJ_H40") (pintype "passive"))
      (node (ref "P2") (pin "H40") (pinfunction "VADJ_H40") (pintype "passive"))
      (node (ref "P4") (pin "80") (pinfunction "80_80") (pintype "passive"))
    )
    (net (code "161") (name "unconnected-(FM1-PadFD0)") (class "Default")
      (node (ref "FM1") (pin "FD0") (pinfunction "FD0_FD0") (pintype "passive"))
    )
    (net (code "162") (name "unconnected-(FM2-PadFD0)") (class "Default")
      (node (ref "FM2") (pin "FD0") (pinfunction "FD0_FD0") (pintype "passive"))
    )
    (net (code "163") (name "unconnected-(FM3-PadFD0)") (class "Default")
      (node (ref "FM3") (pin "FD0") (pinfunction "FD0_FD0") (pintype "passive"))
    )
    (net (code "164") (name "unconnected-(FM4-PadFD0)") (class "Default")
      (node (ref "FM4") (pin "FD0") (pinfunction "FD0_FD0") (pintype "passive"))
    )
    (net (code "165") (name "unconnected-(FM5-PadFD0)") (class "Default")
      (node (ref "FM5") (pin "FD0") (pinfunction "FD0_FD0") (pintype "passive"))
    )
    (net (code "166") (name "unconnected-(FM6-PadFD0)") (class "Default")
      (node (ref "FM6") (pin "FD0") (pinfunction "FD0_FD0") (pintype "passive"))
    )
    (net (code "167") (name "unconnected-(FM7-PadFD0)") (class "Default")
      (node (ref "FM7") (pin "FD0") (pinfunction "FD0_FD0") (pintype "passive"))
    )
    (net (code "168") (name "unconnected-(FM8-PadFD0)") (class "Default")
      (node (ref "FM8") (pin "FD0") (pinfunction "FD0_FD0") (pintype "passive"))
    )
    (net (code "169") (name "unconnected-(MH1-Pad0)") (class "Default")
      (node (ref "MH1") (pin "0") (pinfunction "0_0") (pintype "passive+no_connect"))
    )
    (net (code "170") (name "unconnected-(MH2-Pad0)") (class "Default")
      (node (ref "MH2") (pin "0") (pinfunction "0_0") (pintype "passive+no_connect"))
    )
    (net (code "171") (name "unconnected-(MH3-Pad0)") (class "Default")
      (node (ref "MH3") (pin "0") (pinfunction "0_0") (pintype "passive+no_connect"))
    )
    (net (code "172") (name "unconnected-(MH4-Pad0)") (class "Default")
      (node (ref "MH4") (pin "0") (pinfunction "0_0") (pintype "passive+no_connect"))
    )
  )
)
